# ansible.net
KiCad netlist of a schematic drawn in EAGLE
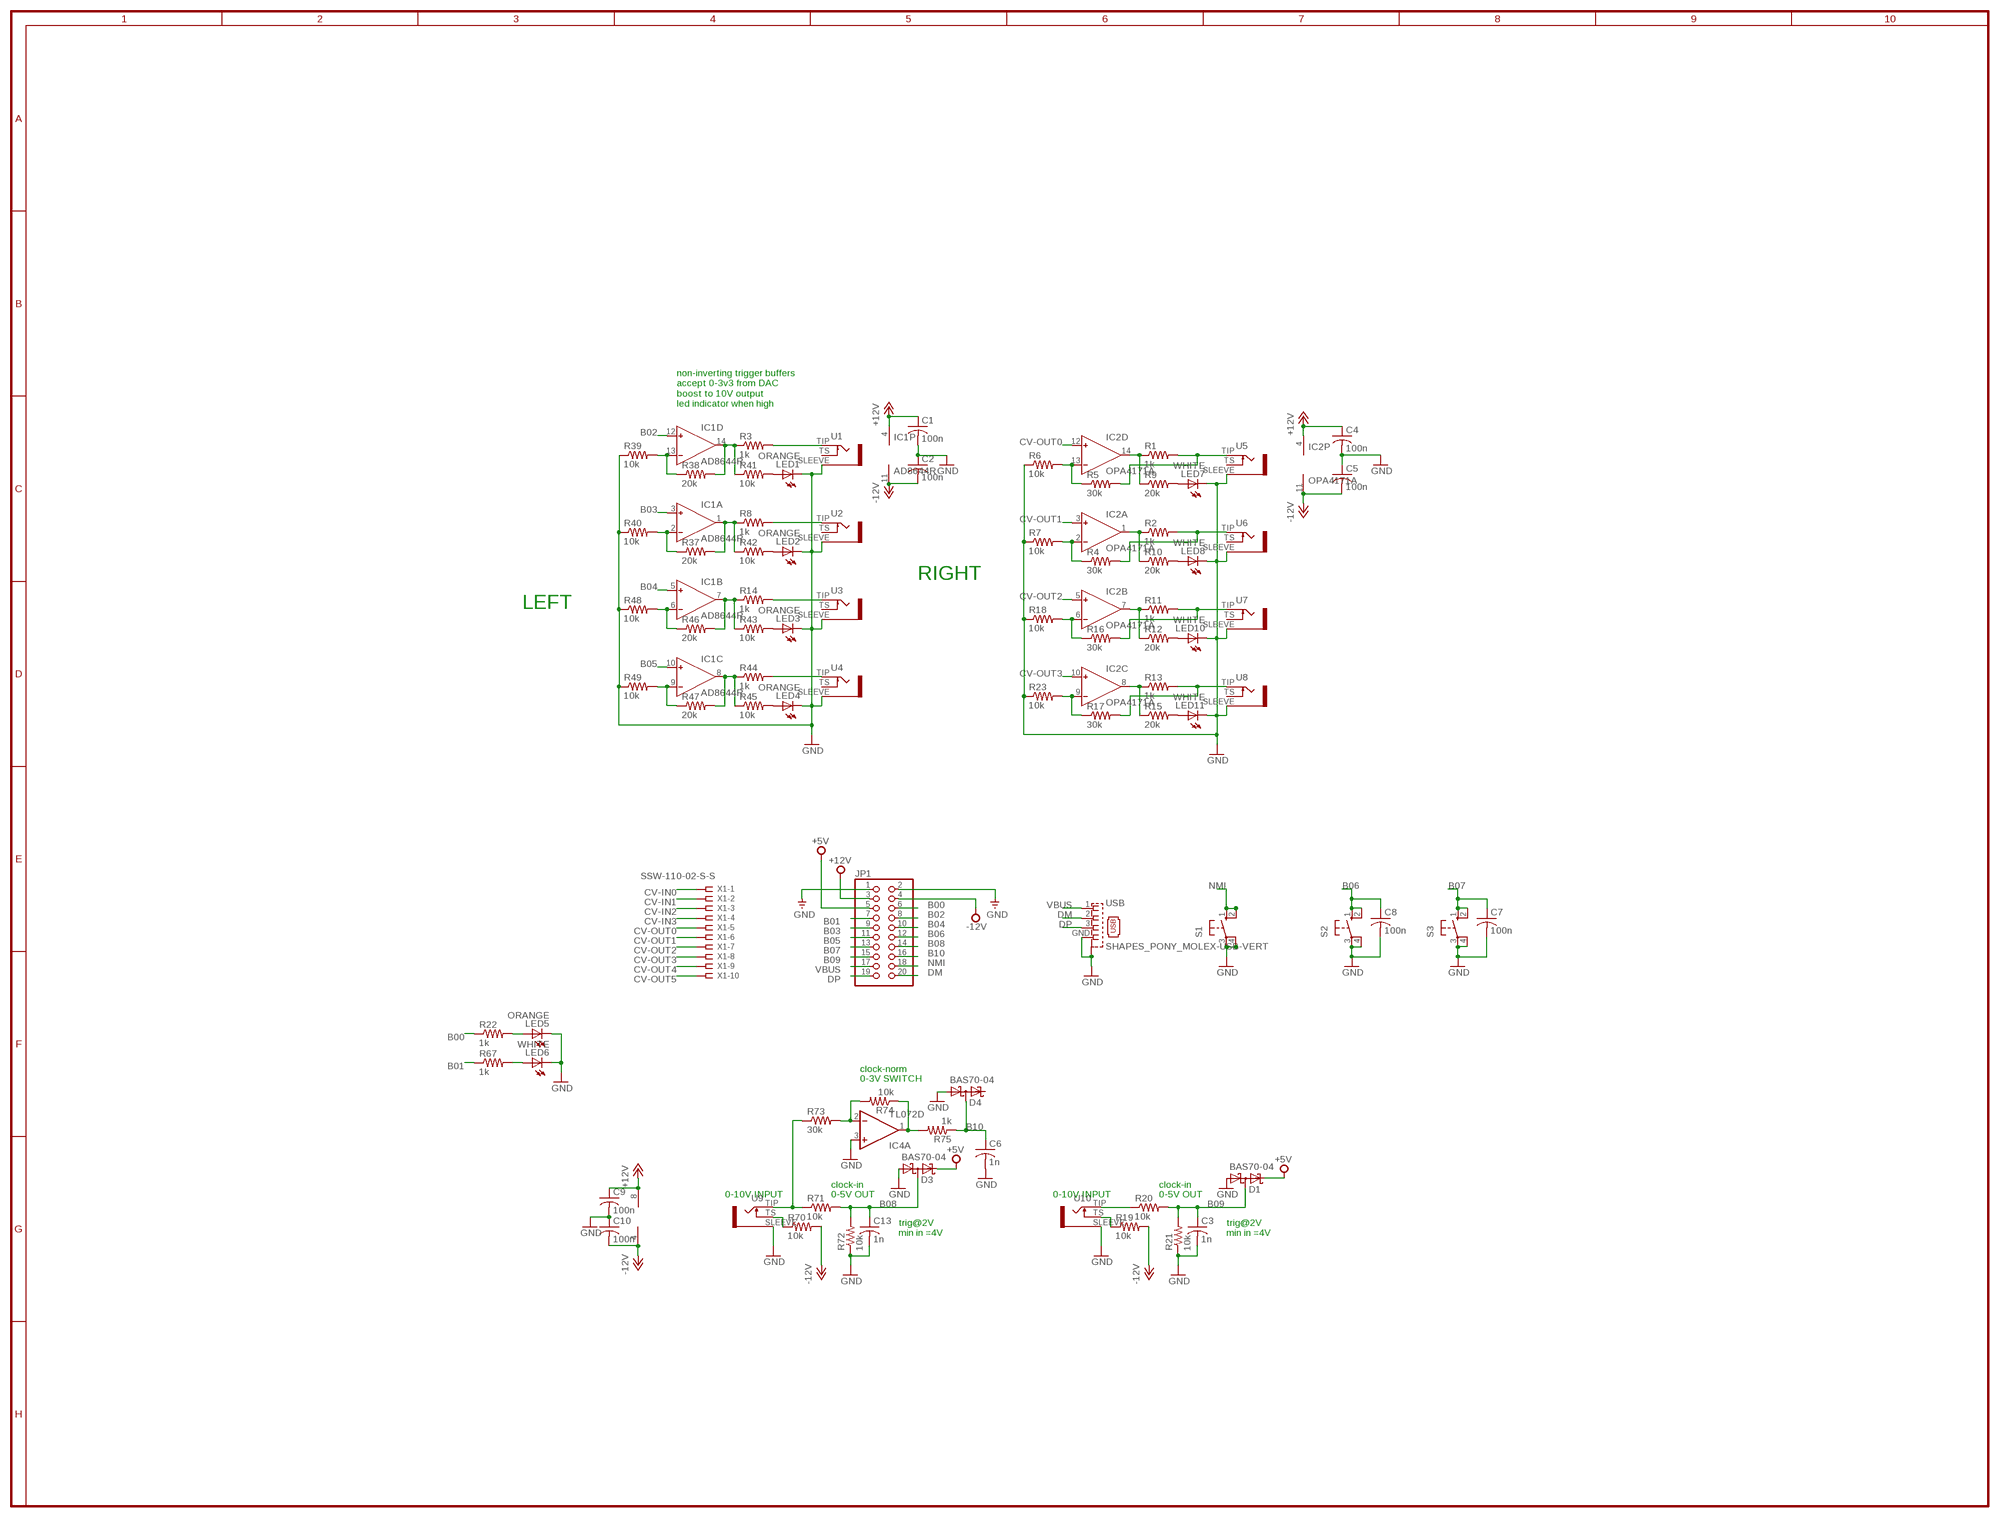
[diagram p0: schematic, sheet 1]

(export (version "E")
  (design (tool "Eeschema 10.0.6"))
  (components
    (comp (ref "C1")
      (value "100n")
      (footprint "eagle-import:C0402")
      (libsource (lib "eagle-import") (part "C-USC0402"))
    )
    (comp (ref "C2")
      (value "100n")
      (footprint "eagle-import:C0402")
      (libsource (lib "eagle-import") (part "C-USC0402"))
    )
    (comp (ref "C3")
      (value "1n")
      (footprint "eagle-import:C0402")
      (libsource (lib "eagle-import") (part "C-USC0402"))
    )
    (comp (ref "C4")
      (value "100n")
      (footprint "eagle-import:C0402")
      (libsource (lib "eagle-import") (part "C-USC0402"))
    )
    (comp (ref "C5")
      (value "100n")
      (footprint "eagle-import:C0402")
      (libsource (lib "eagle-import") (part "C-USC0402"))
    )
    (comp (ref "C6")
      (value "1n")
      (footprint "eagle-import:C0402")
      (libsource (lib "eagle-import") (part "C-USC0402"))
    )
    (comp (ref "C7")
      (value "100n")
      (footprint "eagle-import:C0402")
      (libsource (lib "eagle-import") (part "C-USC0402"))
    )
    (comp (ref "C8")
      (value "100n")
      (footprint "eagle-import:C0402")
      (libsource (lib "eagle-import") (part "C-USC0402"))
    )
    (comp (ref "C9")
      (value "100n")
      (footprint "eagle-import:C0402")
      (libsource (lib "eagle-import") (part "C-USC0402"))
    )
    (comp (ref "C10")
      (value "100n")
      (footprint "eagle-import:C0402")
      (libsource (lib "eagle-import") (part "C-USC0402"))
    )
    (comp (ref "C13")
      (value "1n")
      (footprint "eagle-import:C0402")
      (libsource (lib "eagle-import") (part "C-USC0402"))
    )
    (comp (ref "D1")
      (value "BAS70-04")
      (footprint "eagle-import:SOT23")
      (libsource (lib "eagle-import") (part "BAS70-04"))
    )
    (comp (ref "D3")
      (value "BAS70-04")
      (footprint "eagle-import:SOT23")
      (libsource (lib "eagle-import") (part "BAS70-04"))
    )
    (comp (ref "D4")
      (value "BAS70-04")
      (footprint "eagle-import:SOT23")
      (libsource (lib "eagle-import") (part "BAS70-04"))
    )
    (comp (ref "IC1")
      (value "AD8644R")
      (footprint "eagle-import:SO14")
      (fields (field (name "MF") "ALTERA CORPORATION") (field (name "MPN") "AD8644ARZ"))
      (libsource (lib "eagle-import") (part "AD8644R"))
    )
    (comp (ref "IC2")
      (value "OPA4171A")
      (footprint "eagle-import:SO14")
      (fields (field (name "MF") "ALTERA CORPORATION") (field (name "MPN") "AD8644ARZ"))
      (libsource (lib "eagle-import") (part "AD8644R"))
    )
    (comp (ref "IC4")
      (value "TL072D")
      (footprint "eagle-import:SO08")
      (libsource (lib "eagle-import") (part "TL072D"))
    )
    (comp (ref "JP1")
      (value "PINHD-2X10")
      (footprint "eagle-import:2X10")
      (libsource (lib "eagle-import") (part "PINHD-2X10"))
    )
    (comp (ref "LED1")
      (value "ORANGE")
      (footprint "eagle-import:CHIP-LED0603")
      (libsource (lib "eagle-import") (part "LEDCHIP-LED0603"))
    )
    (comp (ref "LED2")
      (value "ORANGE")
      (footprint "eagle-import:CHIP-LED0603")
      (libsource (lib "eagle-import") (part "LEDCHIP-LED0603"))
    )
    (comp (ref "LED3")
      (value "ORANGE")
      (footprint "eagle-import:CHIP-LED0603")
      (libsource (lib "eagle-import") (part "LEDCHIP-LED0603"))
    )
    (comp (ref "LED4")
      (value "ORANGE")
      (footprint "eagle-import:CHIP-LED0603")
      (libsource (lib "eagle-import") (part "LEDCHIP-LED0603"))
    )
    (comp (ref "LED5")
      (value "ORANGE")
      (footprint "eagle-import:CHIP-LED0603")
      (libsource (lib "eagle-import") (part "LEDCHIP-LED0603"))
    )
    (comp (ref "LED6")
      (value "WHITE")
      (footprint "eagle-import:CHIP-LED0603")
      (libsource (lib "eagle-import") (part "LEDCHIP-LED0603"))
    )
    (comp (ref "LED7")
      (value "WHITE")
      (footprint "eagle-import:CHIP-LED0603")
      (libsource (lib "eagle-import") (part "LEDCHIP-LED0603"))
    )
    (comp (ref "LED8")
      (value "WHITE")
      (footprint "eagle-import:CHIP-LED0603")
      (libsource (lib "eagle-import") (part "LEDCHIP-LED0603"))
    )
    (comp (ref "LED10")
      (value "WHITE")
      (footprint "eagle-import:CHIP-LED0603")
      (libsource (lib "eagle-import") (part "LEDCHIP-LED0603"))
    )
    (comp (ref "LED11")
      (value "WHITE")
      (footprint "eagle-import:CHIP-LED0603")
      (libsource (lib "eagle-import") (part "LEDCHIP-LED0603"))
    )
    (comp (ref "R1")
      (value "1k")
      (footprint "eagle-import:R0402")
      (libsource (lib "eagle-import") (part "R-US_R0402"))
    )
    (comp (ref "R2")
      (value "1k")
      (footprint "eagle-import:R0402")
      (libsource (lib "eagle-import") (part "R-US_R0402"))
    )
    (comp (ref "R3")
      (value "1k")
      (footprint "eagle-import:R0402")
      (libsource (lib "eagle-import") (part "R-US_R0402"))
    )
    (comp (ref "R4")
      (value "30k")
      (footprint "eagle-import:R0402")
      (libsource (lib "eagle-import") (part "R-US_R0402"))
    )
    (comp (ref "R5")
      (value "30k")
      (footprint "eagle-import:R0402")
      (libsource (lib "eagle-import") (part "R-US_R0402"))
    )
    (comp (ref "R6")
      (value "10k")
      (footprint "eagle-import:R0402")
      (libsource (lib "eagle-import") (part "R-US_R0402"))
    )
    (comp (ref "R7")
      (value "10k")
      (footprint "eagle-import:R0402")
      (libsource (lib "eagle-import") (part "R-US_R0402"))
    )
    (comp (ref "R8")
      (value "1k")
      (footprint "eagle-import:R0402")
      (libsource (lib "eagle-import") (part "R-US_R0402"))
    )
    (comp (ref "R9")
      (value "20k")
      (footprint "eagle-import:R0402")
      (libsource (lib "eagle-import") (part "R-US_R0402"))
    )
    (comp (ref "R10")
      (value "20k")
      (footprint "eagle-import:R0402")
      (libsource (lib "eagle-import") (part "R-US_R0402"))
    )
    (comp (ref "R11")
      (value "1k")
      (footprint "eagle-import:R0402")
      (libsource (lib "eagle-import") (part "R-US_R0402"))
    )
    (comp (ref "R12")
      (value "20k")
      (footprint "eagle-import:R0402")
      (libsource (lib "eagle-import") (part "R-US_R0402"))
    )
    (comp (ref "R13")
      (value "1k")
      (footprint "eagle-import:R0402")
      (libsource (lib "eagle-import") (part "R-US_R0402"))
    )
    (comp (ref "R14")
      (value "1k")
      (footprint "eagle-import:R0402")
      (libsource (lib "eagle-import") (part "R-US_R0402"))
    )
    (comp (ref "R15")
      (value "20k")
      (footprint "eagle-import:R0402")
      (libsource (lib "eagle-import") (part "R-US_R0402"))
    )
    (comp (ref "R16")
      (value "30k")
      (footprint "eagle-import:R0402")
      (libsource (lib "eagle-import") (part "R-US_R0402"))
    )
    (comp (ref "R17")
      (value "30k")
      (footprint "eagle-import:R0402")
      (libsource (lib "eagle-import") (part "R-US_R0402"))
    )
    (comp (ref "R18")
      (value "10k")
      (footprint "eagle-import:R0402")
      (libsource (lib "eagle-import") (part "R-US_R0402"))
    )
    (comp (ref "R19")
      (value "10k")
      (footprint "eagle-import:R0402")
      (libsource (lib "eagle-import") (part "R-US_R0402"))
    )
    (comp (ref "R20")
      (value "10k")
      (footprint "eagle-import:R0402")
      (libsource (lib "eagle-import") (part "R-US_R0402"))
    )
    (comp (ref "R21")
      (value "10k")
      (footprint "eagle-import:R0402")
      (libsource (lib "eagle-import") (part "R-US_R0402"))
    )
    (comp (ref "R22")
      (value "1k")
      (footprint "eagle-import:R0402")
      (libsource (lib "eagle-import") (part "R-US_R0402"))
    )
    (comp (ref "R23")
      (value "10k")
      (footprint "eagle-import:R0402")
      (libsource (lib "eagle-import") (part "R-US_R0402"))
    )
    (comp (ref "R37")
      (value "20k")
      (footprint "eagle-import:R0402")
      (libsource (lib "eagle-import") (part "R-US_R0402"))
    )
    (comp (ref "R38")
      (value "20k")
      (footprint "eagle-import:R0402")
      (libsource (lib "eagle-import") (part "R-US_R0402"))
    )
    (comp (ref "R39")
      (value "10k")
      (footprint "eagle-import:R0402")
      (libsource (lib "eagle-import") (part "R-US_R0402"))
    )
    (comp (ref "R40")
      (value "10k")
      (footprint "eagle-import:R0402")
      (libsource (lib "eagle-import") (part "R-US_R0402"))
    )
    (comp (ref "R41")
      (value "10k")
      (footprint "eagle-import:R0402")
      (libsource (lib "eagle-import") (part "R-US_R0402"))
    )
    (comp (ref "R42")
      (value "10k")
      (footprint "eagle-import:R0402")
      (libsource (lib "eagle-import") (part "R-US_R0402"))
    )
    (comp (ref "R43")
      (value "10k")
      (footprint "eagle-import:R0402")
      (libsource (lib "eagle-import") (part "R-US_R0402"))
    )
    (comp (ref "R44")
      (value "1k")
      (footprint "eagle-import:R0402")
      (libsource (lib "eagle-import") (part "R-US_R0402"))
    )
    (comp (ref "R45")
      (value "10k")
      (footprint "eagle-import:R0402")
      (libsource (lib "eagle-import") (part "R-US_R0402"))
    )
    (comp (ref "R46")
      (value "20k")
      (footprint "eagle-import:R0402")
      (libsource (lib "eagle-import") (part "R-US_R0402"))
    )
    (comp (ref "R47")
      (value "20k")
      (footprint "eagle-import:R0402")
      (libsource (lib "eagle-import") (part "R-US_R0402"))
    )
    (comp (ref "R48")
      (value "10k")
      (footprint "eagle-import:R0402")
      (libsource (lib "eagle-import") (part "R-US_R0402"))
    )
    (comp (ref "R49")
      (value "10k")
      (footprint "eagle-import:R0402")
      (libsource (lib "eagle-import") (part "R-US_R0402"))
    )
    (comp (ref "R67")
      (value "1k")
      (footprint "eagle-import:R0402")
      (libsource (lib "eagle-import") (part "R-US_R0402"))
    )
    (comp (ref "R70")
      (value "10k")
      (footprint "eagle-import:R0402")
      (libsource (lib "eagle-import") (part "R-US_R0402"))
    )
    (comp (ref "R71")
      (value "10k")
      (footprint "eagle-import:R0402")
      (libsource (lib "eagle-import") (part "R-US_R0402"))
    )
    (comp (ref "R72")
      (value "10k")
      (footprint "eagle-import:R0402")
      (libsource (lib "eagle-import") (part "R-US_R0402"))
    )
    (comp (ref "R73")
      (value "30k")
      (footprint "eagle-import:R0402")
      (libsource (lib "eagle-import") (part "R-US_R0402"))
    )
    (comp (ref "R74")
      (value "10k")
      (footprint "eagle-import:R0402")
      (libsource (lib "eagle-import") (part "R-US_R0402"))
    )
    (comp (ref "R75")
      (value "1k")
      (footprint "eagle-import:R0402")
      (libsource (lib "eagle-import") (part "R-US_R0402"))
    )
    (comp (ref "S1")
      (value "10-XX")
      (footprint "eagle-import:B3F-10XX")
      (fields (field (name "MPN") "B3F-1000"))
      (libsource (lib "eagle-import") (part "10-XX"))
    )
    (comp (ref "S2")
      (value "10-XX")
      (footprint "eagle-import:B3F-10XX")
      (fields (field (name "MPN") "B3F-1000"))
      (libsource (lib "eagle-import") (part "10-XX"))
    )
    (comp (ref "S3")
      (value "10-XX")
      (footprint "eagle-import:B3F-10XX")
      (fields (field (name "MPN") "B3F-1000"))
      (libsource (lib "eagle-import") (part "10-XX"))
    )
    (comp (ref "U1")
      (value "WQP-PJ301M-12_JACK")
      (footprint "eagle-import:WQP-PJ301M-12_JACK")
      (libsource (lib "eagle-import") (part "WQP-PJ301M-12_JACK"))
    )
    (comp (ref "U2")
      (value "WQP-PJ301M-12_JACK")
      (footprint "eagle-import:WQP-PJ301M-12_JACK")
      (libsource (lib "eagle-import") (part "WQP-PJ301M-12_JACK"))
    )
    (comp (ref "U3")
      (value "WQP-PJ301M-12_JACK")
      (footprint "eagle-import:WQP-PJ301M-12_JACK")
      (libsource (lib "eagle-import") (part "WQP-PJ301M-12_JACK"))
    )
    (comp (ref "U4")
      (value "WQP-PJ301M-12_JACK")
      (footprint "eagle-import:WQP-PJ301M-12_JACK")
      (libsource (lib "eagle-import") (part "WQP-PJ301M-12_JACK"))
    )
    (comp (ref "U5")
      (value "WQP-PJ301M-12_JACK")
      (footprint "eagle-import:WQP-PJ301M-12_JACK")
      (libsource (lib "eagle-import") (part "WQP-PJ301M-12_JACK"))
    )
    (comp (ref "U6")
      (value "WQP-PJ301M-12_JACK")
      (footprint "eagle-import:WQP-PJ301M-12_JACK")
      (libsource (lib "eagle-import") (part "WQP-PJ301M-12_JACK"))
    )
    (comp (ref "U7")
      (value "WQP-PJ301M-12_JACK")
      (footprint "eagle-import:WQP-PJ301M-12_JACK")
      (libsource (lib "eagle-import") (part "WQP-PJ301M-12_JACK"))
    )
    (comp (ref "U8")
      (value "WQP-PJ301M-12_JACK")
      (footprint "eagle-import:WQP-PJ301M-12_JACK")
      (libsource (lib "eagle-import") (part "WQP-PJ301M-12_JACK"))
    )
    (comp (ref "U9")
      (value "WQP-PJ301M-12_JACK")
      (footprint "eagle-import:WQP-PJ301M-12_JACK")
      (libsource (lib "eagle-import") (part "WQP-PJ301M-12_JACK"))
    )
    (comp (ref "U10")
      (value "WQP-PJ301M-12_JACK")
      (footprint "eagle-import:WQP-PJ301M-12_JACK")
      (libsource (lib "eagle-import") (part "WQP-PJ301M-12_JACK"))
    )
    (comp (ref "USB")
      (value "SHAPES_PONY_MOLEX-USB-VERT")
      (footprint "eagle-import:SHAPES_PONY_MOLEX-USB")
      (libsource (lib "eagle-import") (part "SHAPES_PONY_MOLEX-USB-VERT"))
    )
    (comp (ref "X1")
      (value "SSW-110-02-S-S")
      (footprint "eagle-import:SSW-110-02-S-S")
      (libsource (lib "eagle-import") (part "SSW-110-02-S-S"))
    )
  )
  (nets
    (net (code "1") (name "+5V") (class "Default")
      (node (ref "D1") (pin "2") (pinfunction "C2_2") (pintype "passive"))
      (node (ref "D3") (pin "2") (pinfunction "C2_2") (pintype "passive"))
      (node (ref "JP1") (pin "5") (pinfunction "5_5") (pintype "passive"))
    )
    (net (code "2") (name "+12V") (class "Default")
      (node (ref "C1") (pin "1") (pinfunction "1_1") (pintype "passive"))
      (node (ref "C4") (pin "1") (pinfunction "1_1") (pintype "passive"))
      (node (ref "C9") (pin "1") (pinfunction "1_1") (pintype "passive"))
      (node (ref "IC1") (pin "4") (pinfunction "V+_4") (pintype "power_in"))
      (node (ref "IC2") (pin "4") (pinfunction "V+_4") (pintype "power_in"))
      (node (ref "IC4") (pin "8") (pinfunction "V+_8") (pintype "power_in"))
      (node (ref "JP1") (pin "3") (pinfunction "3_3") (pintype "passive"))
    )
    (net (code "3") (name "-12V") (class "Default")
      (node (ref "C10") (pin "2") (pinfunction "2_2") (pintype "passive"))
      (node (ref "C2") (pin "2") (pinfunction "2_2") (pintype "passive"))
      (node (ref "C5") (pin "2") (pinfunction "2_2") (pintype "passive"))
      (node (ref "IC1") (pin "11") (pinfunction "V-_11") (pintype "power_in"))
      (node (ref "IC2") (pin "11") (pinfunction "V-_11") (pintype "power_in"))
      (node (ref "IC4") (pin "4") (pinfunction "V-_4") (pintype "power_in"))
      (node (ref "JP1") (pin "4") (pinfunction "4_4") (pintype "passive"))
      (node (ref "R19") (pin "2") (pinfunction "2_2") (pintype "passive"))
      (node (ref "R70") (pin "2") (pinfunction "2_2") (pintype "passive"))
    )
    (net (code "4") (name "/B00") (class "Default")
      (node (ref "JP1") (pin "6") (pinfunction "6_6") (pintype "passive"))
      (node (ref "R22") (pin "1") (pinfunction "1_1") (pintype "passive"))
    )
    (net (code "5") (name "/B01") (class "Default")
      (node (ref "JP1") (pin "7") (pinfunction "7_7") (pintype "passive"))
      (node (ref "R67") (pin "1") (pinfunction "1_1") (pintype "passive"))
    )
    (net (code "6") (name "/B02") (class "Default")
      (node (ref "IC1") (pin "12") (pinfunction "IN+_12") (pintype "input"))
      (node (ref "JP1") (pin "8") (pinfunction "8_8") (pintype "passive"))
    )
    (net (code "7") (name "/B03") (class "Default")
      (node (ref "IC1") (pin "3") (pinfunction "IN+_3") (pintype "input"))
      (node (ref "JP1") (pin "9") (pinfunction "9_9") (pintype "passive"))
    )
    (net (code "8") (name "/B04") (class "Default")
      (node (ref "IC1") (pin "5") (pinfunction "IN+_5") (pintype "input"))
      (node (ref "JP1") (pin "10") (pinfunction "10_10") (pintype "passive"))
    )
    (net (code "9") (name "/B05") (class "Default")
      (node (ref "IC1") (pin "10") (pinfunction "IN+_10") (pintype "input"))
      (node (ref "JP1") (pin "11") (pinfunction "11_11") (pintype "passive"))
    )
    (net (code "10") (name "/B06") (class "Default")
      (node (ref "C8") (pin "1") (pinfunction "1_1") (pintype "passive"))
      (node (ref "JP1") (pin "12") (pinfunction "12_12") (pintype "passive"))
      (node (ref "S2") (pin "1") (pinfunction "S_1") (pintype "passive"))
      (node (ref "S2") (pin "2") (pinfunction "S1_2") (pintype "passive"))
    )
    (net (code "11") (name "/B07") (class "Default")
      (node (ref "C7") (pin "1") (pinfunction "1_1") (pintype "passive"))
      (node (ref "JP1") (pin "13") (pinfunction "13_13") (pintype "passive"))
      (node (ref "S3") (pin "1") (pinfunction "S_1") (pintype "passive"))
      (node (ref "S3") (pin "2") (pinfunction "S1_2") (pintype "passive"))
    )
    (net (code "12") (name "/B08") (class "Default")
      (node (ref "C13") (pin "1") (pinfunction "1_1") (pintype "passive"))
      (node (ref "D3") (pin "3") (pinfunction "C1A2_3") (pintype "passive"))
      (node (ref "JP1") (pin "14") (pinfunction "14_14") (pintype "passive"))
      (node (ref "R71") (pin "2") (pinfunction "2_2") (pintype "passive"))
      (node (ref "R72") (pin "2") (pinfunction "2_2") (pintype "passive"))
    )
    (net (code "13") (name "/B09") (class "Default")
      (node (ref "C3") (pin "1") (pinfunction "1_1") (pintype "passive"))
      (node (ref "D1") (pin "3") (pinfunction "C1A2_3") (pintype "passive"))
      (node (ref "JP1") (pin "15") (pinfunction "15_15") (pintype "passive"))
      (node (ref "R20") (pin "2") (pinfunction "2_2") (pintype "passive"))
      (node (ref "R21") (pin "2") (pinfunction "2_2") (pintype "passive"))
    )
    (net (code "14") (name "/B10") (class "Default")
      (node (ref "C6") (pin "1") (pinfunction "1_1") (pintype "passive"))
      (node (ref "D4") (pin "3") (pinfunction "C1A2_3") (pintype "passive"))
      (node (ref "JP1") (pin "16") (pinfunction "16_16") (pintype "passive"))
      (node (ref "R75") (pin "1") (pinfunction "1_1") (pintype "passive"))
    )
    (net (code "15") (name "/CV-IN0") (class "Default")
      (node (ref "X1") (pin "1") (pinfunction "1_1") (pintype "passive"))
    )
    (net (code "16") (name "/CV-IN1") (class "Default")
      (node (ref "X1") (pin "2") (pinfunction "1_2") (pintype "passive"))
    )
    (net (code "17") (name "/CV-IN2") (class "Default")
      (node (ref "X1") (pin "3") (pinfunction "1_3") (pintype "passive"))
    )
    (net (code "18") (name "/CV-IN3") (class "Default")
      (node (ref "X1") (pin "4") (pinfunction "1_4") (pintype "passive"))
    )
    (net (code "19") (name "/CV-OUT0") (class "Default")
      (node (ref "IC2") (pin "12") (pinfunction "IN+_12") (pintype "input"))
      (node (ref "X1") (pin "5") (pinfunction "1_5") (pintype "passive"))
    )
    (net (code "20") (name "/CV-OUT1") (class "Default")
      (node (ref "IC2") (pin "3") (pinfunction "IN+_3") (pintype "input"))
      (node (ref "X1") (pin "6") (pinfunction "1_6") (pintype "passive"))
    )
    (net (code "21") (name "/CV-OUT2") (class "Default")
      (node (ref "IC2") (pin "5") (pinfunction "IN+_5") (pintype "input"))
      (node (ref "X1") (pin "7") (pinfunction "1_7") (pintype "passive"))
    )
    (net (code "22") (name "/CV-OUT3") (class "Default")
      (node (ref "IC2") (pin "10") (pinfunction "IN+_10") (pintype "input"))
      (node (ref "X1") (pin "8") (pinfunction "1_8") (pintype "passive"))
    )
    (net (code "23") (name "/CV-OUT4") (class "Default")
      (node (ref "X1") (pin "9") (pinfunction "1_9") (pintype "passive"))
    )
    (net (code "24") (name "/CV-OUT5") (class "Default")
      (node (ref "X1") (pin "10") (pinfunction "1_10") (pintype "passive"))
    )
    (net (code "25") (name "/DM") (class "Default")
      (node (ref "JP1") (pin "20") (pinfunction "20_20") (pintype "passive"))
      (node (ref "USB") (pin "2") (pinfunction "2_2") (pintype "passive"))
    )
    (net (code "26") (name "/DP") (class "Default")
      (node (ref "JP1") (pin "19") (pinfunction "19_19") (pintype "passive"))
      (node (ref "USB") (pin "3") (pinfunction "3_3") (pintype "passive"))
    )
    (net (code "27") (name "/NMI") (class "Default")
      (node (ref "JP1") (pin "18") (pinfunction "18_18") (pintype "passive"))
      (node (ref "S1") (pin "1") (pinfunction "S_1") (pintype "passive"))
      (node (ref "S1") (pin "2") (pinfunction "S1_2") (pintype "passive"))
    )
    (net (code "28") (name "/VBUS") (class "Default")
      (node (ref "JP1") (pin "17") (pinfunction "17_17") (pintype "passive"))
      (node (ref "USB") (pin "1") (pinfunction "1_1") (pintype "passive"))
    )
    (net (code "29") (name "GND") (class "Default")
      (node (ref "C1") (pin "2") (pinfunction "2_2") (pintype "passive"))
      (node (ref "C10") (pin "1") (pinfunction "1_1") (pintype "passive"))
      (node (ref "C13") (pin "2") (pinfunction "2_2") (pintype "passive"))
      (node (ref "C2") (pin "1") (pinfunction "1_1") (pintype "passive"))
      (node (ref "C3") (pin "2") (pinfunction "2_2") (pintype "passive"))
      (node (ref "C4") (pin "2") (pinfunction "2_2") (pintype "passive"))
      (node (ref "C5") (pin "1") (pinfunction "1_1") (pintype "passive"))
      (node (ref "C6") (pin "2") (pinfunction "2_2") (pintype "passive"))
      (node (ref "C7") (pin "2") (pinfunction "2_2") (pintype "passive"))
      (node (ref "C8") (pin "2") (pinfunction "2_2") (pintype "passive"))
      (node (ref "C9") (pin "2") (pinfunction "2_2") (pintype "passive"))
      (node (ref "D1") (pin "1") (pinfunction "A1_1") (pintype "passive"))
      (node (ref "D3") (pin "1") (pinfunction "A1_1") (pintype "passive"))
      (node (ref "D4") (pin "1") (pinfunction "A1_1") (pintype "passive"))
      (node (ref "IC4") (pin "3") (pinfunction "+IN_3") (pintype "input"))
      (node (ref "JP1") (pin "1") (pinfunction "1_1") (pintype "passive"))
      (node (ref "JP1") (pin "2") (pinfunction "2_2") (pintype "passive"))
      (node (ref "LED1") (pin "C") (pinfunction "C_C") (pintype "passive"))
      (node (ref "LED10") (pin "C") (pinfunction "C_C") (pintype "passive"))
      (node (ref "LED11") (pin "C") (pinfunction "C_C") (pintype "passive"))
      (node (ref "LED2") (pin "C") (pinfunction "C_C") (pintype "passive"))
      (node (ref "LED3") (pin "C") (pinfunction "C_C") (pintype "passive"))
      (node (ref "LED4") (pin "C") (pinfunction "C_C") (pintype "passive"))
      (node (ref "LED5") (pin "C") (pinfunction "C_C") (pintype "passive"))
      (node (ref "LED6") (pin "C") (pinfunction "C_C") (pintype "passive"))
      (node (ref "LED7") (pin "C") (pinfunction "C_C") (pintype "passive"))
      (node (ref "LED8") (pin "C") (pinfunction "C_C") (pintype "passive"))
      (node (ref "R18") (pin "1") (pinfunction "1_1") (pintype "passive"))
      (node (ref "R21") (pin "1") (pinfunction "1_1") (pintype "passive"))
      (node (ref "R23") (pin "1") (pinfunction "1_1") (pintype "passive"))
      (node (ref "R39") (pin "1") (pinfunction "1_1") (pintype "passive"))
      (node (ref "R40") (pin "1") (pinfunction "1_1") (pintype "passive"))
      (node (ref "R48") (pin "1") (pinfunction "1_1") (pintype "passive"))
      (node (ref "R49") (pin "1") (pinfunction "1_1") (pintype "passive"))
      (node (ref "R6") (pin "1") (pinfunction "1_1") (pintype "passive"))
      (node (ref "R7") (pin "1") (pinfunction "1_1") (pintype "passive"))
      (node (ref "R72") (pin "1") (pinfunction "1_1") (pintype "passive"))
      (node (ref "S1") (pin "3") (pinfunction "P_3") (pintype "passive"))
      (node (ref "S1") (pin "4") (pinfunction "P1_4") (pintype "passive"))
      (node (ref "S2") (pin "3") (pinfunction "P_3") (pintype "passive"))
      (node (ref "S2") (pin "4") (pinfunction "P1_4") (pintype "passive"))
      (node (ref "S3") (pin "3") (pinfunction "P_3") (pintype "passive"))
      (node (ref "S3") (pin "4") (pinfunction "P1_4") (pintype "passive"))
      (node (ref "U1") (pin "SLEEVE") (pinfunction "SLEEVE_SLEEVE") (pintype "passive"))
      (node (ref "U10") (pin "SLEEVE") (pinfunction "SLEEVE_SLEEVE") (pintype "passive"))
      (node (ref "U2") (pin "SLEEVE") (pinfunction "SLEEVE_SLEEVE") (pintype "passive"))
      (node (ref "U3") (pin "SLEEVE") (pinfunction "SLEEVE_SLEEVE") (pintype "passive"))
      (node (ref "U4") (pin "SLEEVE") (pinfunction "SLEEVE_SLEEVE") (pintype "passive"))
      (node (ref "U5") (pin "SLEEVE") (pinfunction "SLEEVE_SLEEVE") (pintype "passive"))
      (node (ref "U6") (pin "SLEEVE") (pinfunction "SLEEVE_SLEEVE") (pintype "passive"))
      (node (ref "U7") (pin "SLEEVE") (pinfunction "SLEEVE_SLEEVE") (pintype "passive"))
      (node (ref "U8") (pin "SLEEVE") (pinfunction "SLEEVE_SLEEVE") (pintype "passive"))
      (node (ref "U9") (pin "SLEEVE") (pinfunction "SLEEVE_SLEEVE") (pintype "passive"))
      (node (ref "USB") (pin "GND") (pinfunction "GND_GND") (pintype "passive"))
      (node (ref "USB") (pin "M1") (pinfunction "S1_M1") (pintype "passive"))
      (node (ref "USB") (pin "M2") (pinfunction "S1_M2") (pintype "passive"))
      (node (ref "USB") (pin "M4") (pinfunction "S1_M4") (pintype "passive"))
    )
    (net (code "30") (name "Net-(IC1A-IN-)") (class "Default")
      (node (ref "IC1") (pin "2") (pinfunction "IN-_2") (pintype "input"))
      (node (ref "R37") (pin "1") (pinfunction "1_1") (pintype "passive"))
      (node (ref "R40") (pin "2") (pinfunction "2_2") (pintype "passive"))
    )
    (net (code "31") (name "Net-(IC1A-OUT)") (class "Default")
      (node (ref "IC1") (pin "1") (pinfunction "OUT_1") (pintype "output"))
      (node (ref "R37") (pin "2") (pinfunction "2_2") (pintype "passive"))
      (node (ref "R42") (pin "1") (pinfunction "1_1") (pintype "passive"))
      (node (ref "R8") (pin "1") (pinfunction "1_1") (pintype "passive"))
    )
    (net (code "32") (name "Net-(IC1B-IN-)") (class "Default")
      (node (ref "IC1") (pin "6") (pinfunction "IN-_6") (pintype "input"))
      (node (ref "R46") (pin "1") (pinfunction "1_1") (pintype "passive"))
      (node (ref "R48") (pin "2") (pinfunction "2_2") (pintype "passive"))
    )
    (net (code "33") (name "Net-(IC1B-OUT)") (class "Default")
      (node (ref "IC1") (pin "7") (pinfunction "OUT_7") (pintype "output"))
      (node (ref "R14") (pin "1") (pinfunction "1_1") (pintype "passive"))
      (node (ref "R43") (pin "1") (pinfunction "1_1") (pintype "passive"))
      (node (ref "R46") (pin "2") (pinfunction "2_2") (pintype "passive"))
    )
    (net (code "34") (name "Net-(IC1C-IN-)") (class "Default")
      (node (ref "IC1") (pin "9") (pinfunction "IN-_9") (pintype "input"))
      (node (ref "R47") (pin "1") (pinfunction "1_1") (pintype "passive"))
      (node (ref "R49") (pin "2") (pinfunction "2_2") (pintype "passive"))
    )
    (net (code "35") (name "Net-(IC1C-OUT)") (class "Default")
      (node (ref "IC1") (pin "8") (pinfunction "OUT_8") (pintype "output"))
      (node (ref "R44") (pin "1") (pinfunction "1_1") (pintype "passive"))
      (node (ref "R45") (pin "1") (pinfunction "1_1") (pintype "passive"))
      (node (ref "R47") (pin "2") (pinfunction "2_2") (pintype "passive"))
    )
    (net (code "36") (name "Net-(IC1D-IN-)") (class "Default")
      (node (ref "IC1") (pin "13") (pinfunction "IN-_13") (pintype "input"))
      (node (ref "R38") (pin "1") (pinfunction "1_1") (pintype "passive"))
      (node (ref "R39") (pin "2") (pinfunction "2_2") (pintype "passive"))
    )
    (net (code "37") (name "Net-(IC1D-OUT)") (class "Default")
      (node (ref "IC1") (pin "14") (pinfunction "OUT_14") (pintype "output"))
      (node (ref "R3") (pin "1") (pinfunction "1_1") (pintype "passive"))
      (node (ref "R38") (pin "2") (pinfunction "2_2") (pintype "passive"))
      (node (ref "R41") (pin "1") (pinfunction "1_1") (pintype "passive"))
    )
    (net (code "38") (name "Net-(IC2A-IN-)") (class "Default")
      (node (ref "IC2") (pin "2") (pinfunction "IN-_2") (pintype "input"))
      (node (ref "R4") (pin "1") (pinfunction "1_1") (pintype "passive"))
      (node (ref "R7") (pin "2") (pinfunction "2_2") (pintype "passive"))
    )
    (net (code "39") (name "Net-(IC2A-OUT)") (class "Default")
      (node (ref "IC2") (pin "1") (pinfunction "OUT_1") (pintype "output"))
      (node (ref "R10") (pin "1") (pinfunction "1_1") (pintype "passive"))
      (node (ref "R2") (pin "1") (pinfunction "1_1") (pintype "passive"))
    )
    (net (code "40") (name "Net-(IC2B-IN-)") (class "Default")
      (node (ref "IC2") (pin "6") (pinfunction "IN-_6") (pintype "input"))
      (node (ref "R16") (pin "1") (pinfunction "1_1") (pintype "passive"))
      (node (ref "R18") (pin "2") (pinfunction "2_2") (pintype "passive"))
    )
    (net (code "41") (name "Net-(IC2B-OUT)") (class "Default")
      (node (ref "IC2") (pin "7") (pinfunction "OUT_7") (pintype "output"))
      (node (ref "R11") (pin "1") (pinfunction "1_1") (pintype "passive"))
      (node (ref "R12") (pin "1") (pinfunction "1_1") (pintype "passive"))
    )
    (net (code "42") (name "Net-(IC2C-IN-)") (class "Default")
      (node (ref "IC2") (pin "9") (pinfunction "IN-_9") (pintype "input"))
      (node (ref "R17") (pin "1") (pinfunction "1_1") (pintype "passive"))
      (node (ref "R23") (pin "2") (pinfunction "2_2") (pintype "passive"))
    )
    (net (code "43") (name "Net-(IC2C-OUT)") (class "Default")
      (node (ref "IC2") (pin "8") (pinfunction "OUT_8") (pintype "output"))
      (node (ref "R13") (pin "1") (pinfunction "1_1") (pintype "passive"))
      (node (ref "R15") (pin "1") (pinfunction "1_1") (pintype "passive"))
    )
    (net (code "44") (name "Net-(IC2D-IN-)") (class "Default")
      (node (ref "IC2") (pin "13") (pinfunction "IN-_13") (pintype "input"))
      (node (ref "R5") (pin "1") (pinfunction "1_1") (pintype "passive"))
      (node (ref "R6") (pin "2") (pinfunction "2_2") (pintype "passive"))
    )
    (net (code "45") (name "Net-(IC2D-OUT)") (class "Default")
      (node (ref "IC2") (pin "14") (pinfunction "OUT_14") (pintype "output"))
      (node (ref "R1") (pin "1") (pinfunction "1_1") (pintype "passive"))
      (node (ref "R9") (pin "1") (pinfunction "1_1") (pintype "passive"))
    )
    (net (code "46") (name "Net-(IC4A--IN)") (class "Default")
      (node (ref "IC4") (pin "2") (pinfunction "-IN_2") (pintype "input"))
      (node (ref "R73") (pin "2") (pinfunction "2_2") (pintype "passive"))
      (node (ref "R74") (pin "2") (pinfunction "2_2") (pintype "passive"))
    )
    (net (code "47") (name "Net-(IC4A-OUT)") (class "Default")
      (node (ref "IC4") (pin "1") (pinfunction "OUT_1") (pintype "output"))
      (node (ref "R74") (pin "1") (pinfunction "1_1") (pintype "passive"))
      (node (ref "R75") (pin "2") (pinfunction "2_2") (pintype "passive"))
    )
    (net (code "48") (name "Net-(LED1-PadA)") (class "Default")
      (node (ref "LED1") (pin "A") (pinfunction "A_A") (pintype "passive"))
      (node (ref "R41") (pin "2") (pinfunction "2_2") (pintype "passive"))
    )
    (net (code "49") (name "Net-(LED2-PadA)") (class "Default")
      (node (ref "LED2") (pin "A") (pinfunction "A_A") (pintype "passive"))
      (node (ref "R42") (pin "2") (pinfunction "2_2") (pintype "passive"))
    )
    (net (code "50") (name "Net-(LED3-PadA)") (class "Default")
      (node (ref "LED3") (pin "A") (pinfunction "A_A") (pintype "passive"))
      (node (ref "R43") (pin "2") (pinfunction "2_2") (pintype "passive"))
    )
    (net (code "51") (name "Net-(LED4-PadA)") (class "Default")
      (node (ref "LED4") (pin "A") (pinfunction "A_A") (pintype "passive"))
      (node (ref "R45") (pin "2") (pinfunction "2_2") (pintype "passive"))
    )
    (net (code "52") (name "Net-(LED5-PadA)") (class "Default")
      (node (ref "LED5") (pin "A") (pinfunction "A_A") (pintype "passive"))
      (node (ref "R22") (pin "2") (pinfunction "2_2") (pintype "passive"))
    )
    (net (code "53") (name "Net-(LED6-PadA)") (class "Default")
      (node (ref "LED6") (pin "A") (pinfunction "A_A") (pintype "passive"))
      (node (ref "R67") (pin "2") (pinfunction "2_2") (pintype "passive"))
    )
    (net (code "54") (name "Net-(LED7-PadA)") (class "Default")
      (node (ref "LED7") (pin "A") (pinfunction "A_A") (pintype "passive"))
      (node (ref "R9") (pin "2") (pinfunction "2_2") (pintype "passive"))
    )
    (net (code "55") (name "Net-(LED8-PadA)") (class "Default")
      (node (ref "LED8") (pin "A") (pinfunction "A_A") (pintype "passive"))
      (node (ref "R10") (pin "2") (pinfunction "2_2") (pintype "passive"))
    )
    (net (code "56") (name "Net-(LED10-PadA)") (class "Default")
      (node (ref "LED10") (pin "A") (pinfunction "A_A") (pintype "passive"))
      (node (ref "R12") (pin "2") (pinfunction "2_2") (pintype "passive"))
    )
    (net (code "57") (name "Net-(LED11-PadA)") (class "Default")
      (node (ref "LED11") (pin "A") (pinfunction "A_A") (pintype "passive"))
      (node (ref "R15") (pin "2") (pinfunction "2_2") (pintype "passive"))
    )
    (net (code "58") (name "Net-(R1-Pad2)") (class "Default")
      (node (ref "R1") (pin "2") (pinfunction "2_2") (pintype "passive"))
      (node (ref "R5") (pin "2") (pinfunction "2_2") (pintype "passive"))
      (node (ref "U5") (pin "TIP") (pinfunction "TIP_TIP") (pintype "passive"))
    )
    (net (code "59") (name "Net-(R2-Pad2)") (class "Default")
      (node (ref "R2") (pin "2") (pinfunction "2_2") (pintype "passive"))
      (node (ref "R4") (pin "2") (pinfunction "2_2") (pintype "passive"))
      (node (ref "U6") (pin "TIP") (pinfunction "TIP_TIP") (pintype "passive"))
    )
    (net (code "60") (name "Net-(R3-Pad2)") (class "Default")
      (node (ref "R3") (pin "2") (pinfunction "2_2") (pintype "passive"))
      (node (ref "U1") (pin "TIP") (pinfunction "TIP_TIP") (pintype "passive"))
    )
    (net (code "61") (name "Net-(R8-Pad2)") (class "Default")
      (node (ref "R8") (pin "2") (pinfunction "2_2") (pintype "passive"))
      (node (ref "U2") (pin "TIP") (pinfunction "TIP_TIP") (pintype "passive"))
    )
    (net (code "62") (name "Net-(R11-Pad2)") (class "Default")
      (node (ref "R11") (pin "2") (pinfunction "2_2") (pintype "passive"))
      (node (ref "R16") (pin "2") (pinfunction "2_2") (pintype "passive"))
      (node (ref "U7") (pin "TIP") (pinfunction "TIP_TIP") (pintype "passive"))
    )
    (net (code "63") (name "Net-(R13-Pad2)") (class "Default")
      (node (ref "R13") (pin "2") (pinfunction "2_2") (pintype "passive"))
      (node (ref "R17") (pin "2") (pinfunction "2_2") (pintype "passive"))
      (node (ref "U8") (pin "TIP") (pinfunction "TIP_TIP") (pintype "passive"))
    )
    (net (code "64") (name "Net-(R14-Pad2)") (class "Default")
      (node (ref "R14") (pin "2") (pinfunction "2_2") (pintype "passive"))
      (node (ref "U3") (pin "TIP") (pinfunction "TIP_TIP") (pintype "passive"))
    )
    (net (code "65") (name "Net-(R19-Pad1)") (class "Default")
      (node (ref "R19") (pin "1") (pinfunction "1_1") (pintype "passive"))
      (node (ref "U10") (pin "TS") (pinfunction "TS_TS") (pintype "passive"))
    )
    (net (code "66") (name "Net-(R20-Pad1)") (class "Default")
      (node (ref "R20") (pin "1") (pinfunction "1_1") (pintype "passive"))
      (node (ref "U10") (pin "TIP") (pinfunction "TIP_TIP") (pintype "passive"))
    )
    (net (code "67") (name "Net-(R44-Pad2)") (class "Default")
      (node (ref "R44") (pin "2") (pinfunction "2_2") (pintype "passive"))
      (node (ref "U4") (pin "TIP") (pinfunction "TIP_TIP") (pintype "passive"))
    )
    (net (code "68") (name "Net-(R70-Pad1)") (class "Default")
      (node (ref "R70") (pin "1") (pinfunction "1_1") (pintype "passive"))
      (node (ref "U9") (pin "TS") (pinfunction "TS_TS") (pintype "passive"))
    )
    (net (code "69") (name "Net-(R71-Pad1)") (class "Default")
      (node (ref "R71") (pin "1") (pinfunction "1_1") (pintype "passive"))
      (node (ref "R73") (pin "1") (pinfunction "1_1") (pintype "passive"))
      (node (ref "U9") (pin "TIP") (pinfunction "TIP_TIP") (pintype "passive"))
    )
    (net (code "70") (name "unconnected-(D4-C2-Pad2)") (class "Default")
      (node (ref "D4") (pin "2") (pinfunction "C2_2") (pintype "passive"))
    )
    (net (code "71") (name "unconnected-(U1-PadTS)") (class "Default")
      (node (ref "U1") (pin "TS") (pinfunction "TS_TS") (pintype "passive"))
    )
    (net (code "72") (name "unconnected-(U2-PadTS)") (class "Default")
      (node (ref "U2") (pin "TS") (pinfunction "TS_TS") (pintype "passive"))
    )
    (net (code "73") (name "unconnected-(U3-PadTS)") (class "Default")
      (node (ref "U3") (pin "TS") (pinfunction "TS_TS") (pintype "passive"))
    )
    (net (code "74") (name "unconnected-(U4-PadTS)") (class "Default")
      (node (ref "U4") (pin "TS") (pinfunction "TS_TS") (pintype "passive"))
    )
    (net (code "75") (name "unconnected-(U5-PadTS)") (class "Default")
      (node (ref "U5") (pin "TS") (pinfunction "TS_TS") (pintype "passive"))
    )
    (net (code "76") (name "unconnected-(U6-PadTS)") (class "Default")
      (node (ref "U6") (pin "TS") (pinfunction "TS_TS") (pintype "passive"))
    )
    (net (code "77") (name "unconnected-(U7-PadTS)") (class "Default")
      (node (ref "U7") (pin "TS") (pinfunction "TS_TS") (pintype "passive"))
    )
    (net (code "78") (name "unconnected-(U8-PadTS)") (class "Default")
      (node (ref "U8") (pin "TS") (pinfunction "TS_TS") (pintype "passive"))
    )
  )
)
